# UART_Interface.net
KiCad netlist of a schematic drawn in Altium Designer
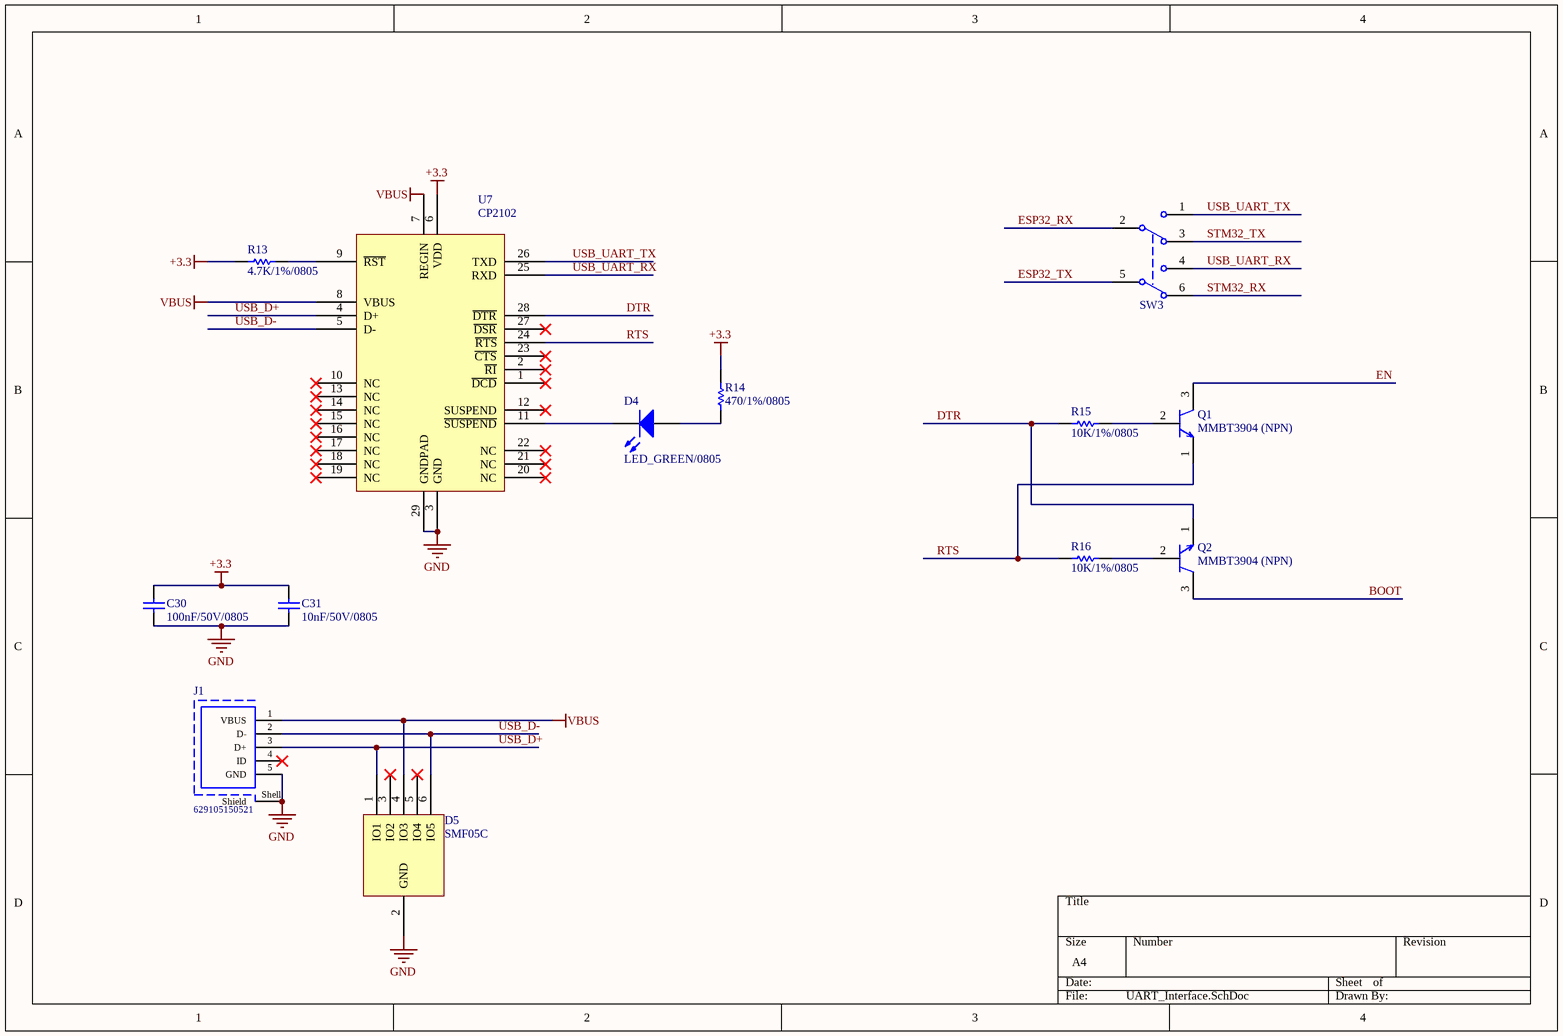
[diagram p0: UART_Interface.SchDoc]

(export (version "E")
  (design (tool "Eeschema 10.0.6"))
  (components
    (comp (ref "C30")
      (value "100nF/50V/0805")
      (footprint "CAP-SM-0805")
      (description "Capacitor")
      (fields (field (name "Comment") "Cap Non-Pol SMD"))
      (libsource (lib "PIF_Library") (part "Cap Non-Pol SMD"))
    )
    (comp (ref "C31")
      (value "10nF/50V/0805")
      (footprint "CAP-SM-0805")
      (description "Capacitor")
      (fields (field (name "Comment") "Cap Non-Pol SMD"))
      (libsource (lib "PIF_Library") (part "Cap Non-Pol SMD"))
    )
    (comp (ref "D4")
      (value "LED_GREEN/0805")
      (footprint "LED_0805_Blue")
      (description "LED")
      (libsource (lib "PIF_Library") (part "LED SMD"))
    )
    (comp (ref "D5")
      (value "SMF05C")
      (footprint "SOT65P210X110-6N")
      (libsource (lib "MiclsLib") (part "SMF05C"))
    )
    (comp (ref "J1")
      (value "629105150521")
      (footprint "629105150521")
      (description "Micro USB 2.0 Type B Receptacle WR-COM, Horizontal, SMT, with Pegs, High Current at Pin 1 & Pin 5")
      (fields (field (name "PUBLISHER") "Wurth Elektronik"))
      (libsource (lib "ALTIUM-WR-COM_USB_20-rev18d") (part "629105150521"))
    )
    (comp (ref "Q1")
      (value "MMBT3904 (NPN)")
      (footprint "SOT95P245X110-3N")
      (fields (field (name "MANUFACTURER") "On Semiconductor"))
      (libsource (lib "MiclsLib") (part "MMBT3904 (NPN)"))
    )
    (comp (ref "Q2")
      (value "MMBT3904 (NPN)")
      (footprint "SOT95P245X110-3N")
      (fields (field (name "MANUFACTURER") "On Semiconductor"))
      (libsource (lib "MiclsLib") (part "MMBT3904 (NPN)"))
    )
    (comp (ref "R13")
      (value "4.7K/1%/0805")
      (footprint "RES-SM-0805")
      (description "Resistor")
      (fields (field (name "Comment") "RESISTOR SMD"))
      (libsource (lib "PIF_Library") (part "RESISTOR SMD"))
    )
    (comp (ref "R14")
      (value "470/1%/0805")
      (footprint "RES-SM-0805")
      (description "Resistor")
      (fields (field (name "Comment") "RESISTOR SMD"))
      (libsource (lib "PIF_Library") (part "RESISTOR SMD"))
    )
    (comp (ref "R15")
      (value "10K/1%/0805")
      (footprint "RES-SM-0805")
      (description "Resistor")
      (fields (field (name "Comment") "RESISTOR SMD"))
      (libsource (lib "PIF_Library") (part "RESISTOR SMD"))
    )
    (comp (ref "R16")
      (value "10K/1%/0805")
      (footprint "RES-SM-0805")
      (description "Resistor")
      (fields (field (name "Comment") "RESISTOR SMD"))
      (libsource (lib "PIF_Library") (part "RESISTOR SMD"))
    )
    (comp (ref "SW3")
      (value "452404020202")
      (footprint "452404020202")
      (description "WS-SLTV THT Mini Slide Switch, Same Side Connection, DPDT, 6VDC, 300mA, 450g")
      (fields (field (name "MANUFACTURER") "Wurth Elektronik"))
      (libsource (lib "Altium_WS-SLTV (rev22a)") (part "452404020202"))
    )
    (comp (ref "U7")
      (value "CP2102")
      (footprint "QFN50P500X500X90_HS-29N")
      (libsource (lib "MiclsLib") (part "CP2102"))
    )
  )
  (nets
    (net (code "1") (name "+3.3") (class "Default")
      (node (ref "C30") (pin "1") (pinfunction "1_1") (pintype "passive"))
      (node (ref "C31") (pin "1") (pinfunction "1_1") (pintype "passive"))
      (node (ref "R13") (pin "2") (pinfunction "2_2") (pintype "passive"))
      (node (ref "R14") (pin "1") (pinfunction "1_1") (pintype "passive"))
      (node (ref "U7") (pin "6") (pinfunction "VDD_6") (pintype "passive"))
    )
    (net (code "2") (name "/BOOT") (class "Default")
      (node (ref "Q2") (pin "3") (pinfunction "3_3") (pintype "passive"))
    )
    (net (code "3") (name "/DTR") (class "Default")
      (node (ref "Q2") (pin "1") (pinfunction "1_1") (pintype "passive"))
      (node (ref "R15") (pin "2") (pinfunction "2_2") (pintype "passive"))
      (node (ref "U7") (pin "28") (pinfunction "~{DTR}_28") (pintype "passive"))
    )
    (net (code "4") (name "/EN") (class "Default")
      (node (ref "Q1") (pin "3") (pinfunction "3_3") (pintype "passive"))
    )
    (net (code "5") (name "/ESP32_RX") (class "Default")
      (node (ref "SW3") (pin "2") (pinfunction "COM_2") (pintype "passive"))
    )
    (net (code "6") (name "/ESP32_TX") (class "Default")
      (node (ref "SW3") (pin "5") (pinfunction "COM_5") (pintype "passive"))
    )
    (net (code "7") (name "/RTS") (class "Default")
      (node (ref "Q1") (pin "1") (pinfunction "1_1") (pintype "passive"))
      (node (ref "R16") (pin "2") (pinfunction "2_2") (pintype "passive"))
      (node (ref "U7") (pin "24") (pinfunction "~{RTS}_24") (pintype "passive"))
    )
    (net (code "8") (name "/STM32_RX") (class "Default")
      (node (ref "SW3") (pin "6") (pinfunction "6_6") (pintype "passive"))
    )
    (net (code "9") (name "/STM32_TX") (class "Default")
      (node (ref "SW3") (pin "3") (pinfunction "3_3") (pintype "passive"))
    )
    (net (code "10") (name "/USB_D+") (class "Default")
      (node (ref "D5") (pin "1") (pinfunction "IO1_1") (pintype "passive"))
      (node (ref "J1") (pin "3") (pinfunction "D+_3") (pintype "passive"))
      (node (ref "U7") (pin "4") (pinfunction "D+_4") (pintype "passive"))
    )
    (net (code "11") (name "/USB_D-") (class "Default")
      (node (ref "D5") (pin "6") (pinfunction "IO5_6") (pintype "passive"))
      (node (ref "J1") (pin "2") (pinfunction "D-_2") (pintype "passive"))
      (node (ref "U7") (pin "5") (pinfunction "D-_5") (pintype "passive"))
    )
    (net (code "12") (name "/USB_UART_RX") (class "Default")
      (node (ref "SW3") (pin "4") (pinfunction "4_4") (pintype "passive"))
      (node (ref "U7") (pin "25") (pinfunction "RXD_25") (pintype "passive"))
    )
    (net (code "13") (name "/USB_UART_TX") (class "Default")
      (node (ref "SW3") (pin "1") (pinfunction "1_1") (pintype "passive"))
      (node (ref "U7") (pin "26") (pinfunction "TXD_26") (pintype "passive"))
    )
    (net (code "14") (name "GND") (class "Default")
      (node (ref "C30") (pin "2") (pinfunction "2_2") (pintype "passive"))
      (node (ref "C31") (pin "2") (pinfunction "2_2") (pintype "passive"))
      (node (ref "D5") (pin "2") (pinfunction "GND_2") (pintype "passive"))
      (node (ref "J1") (pin "5") (pinfunction "GND_5") (pintype "passive"))
      (node (ref "J1") (pin "Shell") (pinfunction "Shield_Shell") (pintype "passive"))
      (node (ref "U7") (pin "29") (pinfunction "GNDPAD_29") (pintype "passive"))
      (node (ref "U7") (pin "3") (pinfunction "GND_3") (pintype "passive"))
    )
    (net (code "15") (name "Net-(D4-A)") (class "Default")
      (node (ref "D4") (pin "1") (pinfunction "A_1") (pintype "passive"))
      (node (ref "R14") (pin "2") (pinfunction "2_2") (pintype "passive"))
    )
    (net (code "16") (name "Net-(D4-K)") (class "Default")
      (node (ref "D4") (pin "2") (pinfunction "K_2") (pintype "passive"))
      (node (ref "U7") (pin "11") (pinfunction "~{SUSPEND}_11") (pintype "passive"))
    )
    (net (code "17") (name "Net-(Q1-Pad2)") (class "Default")
      (node (ref "Q1") (pin "2") (pinfunction "2_2") (pintype "passive"))
      (node (ref "R15") (pin "1") (pinfunction "1_1") (pintype "passive"))
    )
    (net (code "18") (name "Net-(Q2-Pad2)") (class "Default")
      (node (ref "Q2") (pin "2") (pinfunction "2_2") (pintype "passive"))
      (node (ref "R16") (pin "1") (pinfunction "1_1") (pintype "passive"))
    )
    (net (code "19") (name "Net-(U7-~{RST})") (class "Default")
      (node (ref "R13") (pin "1") (pinfunction "1_1") (pintype "passive"))
      (node (ref "U7") (pin "9") (pinfunction "~{RST}_9") (pintype "passive"))
    )
    (net (code "20") (name "VBUS") (class "Default")
      (node (ref "D5") (pin "4") (pinfunction "IO3_4") (pintype "passive"))
      (node (ref "J1") (pin "1") (pinfunction "VBUS_1") (pintype "passive"))
      (node (ref "U7") (pin "7") (pinfunction "REGIN_7") (pintype "passive"))
      (node (ref "U7") (pin "8") (pinfunction "VBUS_8") (pintype "passive"))
    )
    (net (code "21") (name "unconnected-(D5-IO2-Pad3)") (class "Default")
      (node (ref "D5") (pin "3") (pinfunction "IO2_3") (pintype "passive+no_connect"))
    )
    (net (code "22") (name "unconnected-(D5-IO4-Pad5)") (class "Default")
      (node (ref "D5") (pin "5") (pinfunction "IO4_5") (pintype "passive+no_connect"))
    )
    (net (code "23") (name "unconnected-(J1-ID-Pad4)") (class "Default")
      (node (ref "J1") (pin "4") (pinfunction "ID_4") (pintype "passive+no_connect"))
    )
    (net (code "24") (name "unconnected-(U7-NC-Pad10)") (class "Default")
      (node (ref "U7") (pin "10") (pinfunction "NC_10") (pintype "passive+no_connect"))
    )
    (net (code "25") (name "unconnected-(U7-NC-Pad13)") (class "Default")
      (node (ref "U7") (pin "13") (pinfunction "NC_13") (pintype "passive+no_connect"))
    )
    (net (code "26") (name "unconnected-(U7-NC-Pad14)") (class "Default")
      (node (ref "U7") (pin "14") (pinfunction "NC_14") (pintype "passive+no_connect"))
    )
    (net (code "27") (name "unconnected-(U7-NC-Pad15)") (class "Default")
      (node (ref "U7") (pin "15") (pinfunction "NC_15") (pintype "passive+no_connect"))
    )
    (net (code "28") (name "unconnected-(U7-NC-Pad16)") (class "Default")
      (node (ref "U7") (pin "16") (pinfunction "NC_16") (pintype "passive+no_connect"))
    )
    (net (code "29") (name "unconnected-(U7-NC-Pad17)") (class "Default")
      (node (ref "U7") (pin "17") (pinfunction "NC_17") (pintype "passive+no_connect"))
    )
    (net (code "30") (name "unconnected-(U7-NC-Pad18)") (class "Default")
      (node (ref "U7") (pin "18") (pinfunction "NC_18") (pintype "passive+no_connect"))
    )
    (net (code "31") (name "unconnected-(U7-NC-Pad19)") (class "Default")
      (node (ref "U7") (pin "19") (pinfunction "NC_19") (pintype "passive+no_connect"))
    )
    (net (code "32") (name "unconnected-(U7-NC-Pad20)") (class "Default")
      (node (ref "U7") (pin "20") (pinfunction "NC_20") (pintype "passive+no_connect"))
    )
    (net (code "33") (name "unconnected-(U7-NC-Pad21)") (class "Default")
      (node (ref "U7") (pin "21") (pinfunction "NC_21") (pintype "passive+no_connect"))
    )
    (net (code "34") (name "unconnected-(U7-NC-Pad22)") (class "Default")
      (node (ref "U7") (pin "22") (pinfunction "NC_22") (pintype "passive+no_connect"))
    )
    (net (code "35") (name "unconnected-(U7-SUSPEND-Pad12)") (class "Default")
      (node (ref "U7") (pin "12") (pinfunction "SUSPEND_12") (pintype "passive+no_connect"))
    )
    (net (code "36") (name "unconnected-(U7-~{CTS}-Pad23)") (class "Default")
      (node (ref "U7") (pin "23") (pinfunction "~{CTS}_23") (pintype "passive+no_connect"))
    )
    (net (code "37") (name "unconnected-(U7-~{DCD}-Pad1)") (class "Default")
      (node (ref "U7") (pin "1") (pinfunction "~{DCD}_1") (pintype "passive+no_connect"))
    )
    (net (code "38") (name "unconnected-(U7-~{DSR}-Pad27)") (class "Default")
      (node (ref "U7") (pin "27") (pinfunction "~{DSR}_27") (pintype "passive+no_connect"))
    )
    (net (code "39") (name "unconnected-(U7-~{RI}-Pad2)") (class "Default")
      (node (ref "U7") (pin "2") (pinfunction "~{RI}_2") (pintype "passive+no_connect"))
    )
  )
)
